# MARS_PORB.net
KiCad netlist of a schematic drawn in Altium Designer
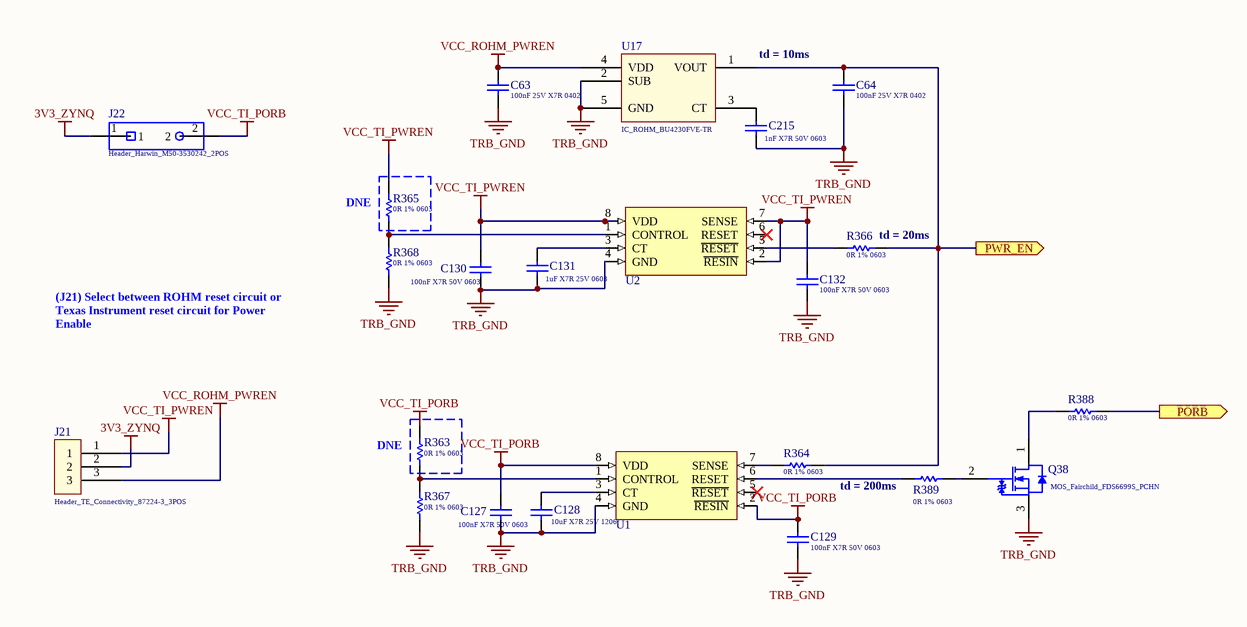
[diagram p0: MARS_PORB.SchDoc]

(export (version "E")
  (design (tool "Eeschema 10.0.6"))
  (components
    (comp (ref "C63")
      (value "Cap_Taiyo_Yuden_TMK105B7104KV-FR_100nF")
      (footprint "Cap_Taiyo_Yuden_TMK105B7104KV-FR_100nF")
      (description "CAP CER 100nF 25V X7R 0402")
      (fields (field (name "CAPACITANCE") "100nF 25V X7R 0402"))
      (libsource (lib "Cap_Taiyo_Yuden_TMK105B7104KV-FR_100nF") (part "Cap_Taiyo_Yuden_TMK105B7104KV-FR_100nF"))
    )
    (comp (ref "C64")
      (value "Cap_Taiyo_Yuden_TMK105B7104KV-FR_100nF")
      (footprint "Cap_Taiyo_Yuden_TMK105B7104KV-FR_100nF")
      (description "CAP CER 100nF 25V X7R 0402")
      (fields (field (name "CAPACITANCE") "100nF 25V X7R 0402"))
      (libsource (lib "Cap_Taiyo_Yuden_TMK105B7104KV-FR_100nF") (part "Cap_Taiyo_Yuden_TMK105B7104KV-FR_100nF"))
    )
    (comp (ref "C127")
      (value "Cap_Kemet_C0603C104M5RACAUTO_100nF")
      (footprint "Cap_Kemet_C0603C104M5RACAUTO_100nF")
      (description "CAP CER 100nF 50V X7R 0603")
      (fields (field (name "CAPACITANCE") "100nF X7R 50V 0603"))
      (libsource (lib "Cap_Kemet_C0603C104M5RACAUTO_100nF") (part "Cap_Kemet_C0603C104M5RACAUTO_100nF"))
    )
    (comp (ref "C128")
      (value "Cap_Murata_GRM31CR71E106MA12L_10uF")
      (footprint "Cap_Murata_GRM31CR71E106MA12L_10uF")
      (description "CAP CER 10uF 25V X7R 1206")
      (fields (field (name "CAPACITANCE") "10uF X7R 25V 1206"))
      (libsource (lib "Cap_Murata_GRM31CR71E106MA12L_10uF") (part "Cap_Murata_GRM31CR71E106MA12L_10uF"))
    )
    (comp (ref "C129")
      (value "Cap_Kemet_C0603C104M5RACAUTO_100nF")
      (footprint "Cap_Kemet_C0603C104M5RACAUTO_100nF")
      (description "CAP CER 100nF 50V X7R 0603")
      (fields (field (name "CAPACITANCE") "100nF X7R 50V 0603"))
      (libsource (lib "Cap_Kemet_C0603C104M5RACAUTO_100nF") (part "Cap_Kemet_C0603C104M5RACAUTO_100nF"))
    )
    (comp (ref "C130")
      (value "Cap_Kemet_C0603C104M5RACAUTO_100nF")
      (footprint "Cap_Kemet_C0603C104M5RACAUTO_100nF")
      (description "CAP CER 100nF 50V X7R 0603")
      (fields (field (name "CAPACITANCE") "100nF X7R 50V 0603"))
      (libsource (lib "Cap_Kemet_C0603C104M5RACAUTO_100nF") (part "Cap_Kemet_C0603C104M5RACAUTO_100nF"))
    )
    (comp (ref "C131")
      (value "Cap_Murata_GCJ188R71E105KA01J_1uF")
      (footprint "Cap_Murata_GCJ188R71E105KA01J_1uF")
      (description "CAP CER 1uF 25V X7R 0603")
      (fields (field (name "CAPACITANCE") "1uF X7R 25V 0603"))
      (libsource (lib "Cap_Murata_GCJ188R71E105KA01J_1uF") (part "Cap_Murata_GCJ188R71E105KA01J_1uF"))
    )
    (comp (ref "C132")
      (value "Cap_Kemet_C0603C104M5RACAUTO_100nF")
      (footprint "Cap_Kemet_C0603C104M5RACAUTO_100nF")
      (description "CAP CER 100nF 50V X7R 0603")
      (fields (field (name "CAPACITANCE") "100nF X7R 50V 0603"))
      (libsource (lib "Cap_Kemet_C0603C104M5RACAUTO_100nF") (part "Cap_Kemet_C0603C104M5RACAUTO_100nF"))
    )
    (comp (ref "C215")
      (value "Cap_Kemet_C0603C102J5RACAUTO_1nF")
      (footprint "Cap_Kemet_C0603C102J5RACAUTO_1nF")
      (description "CAP CER 1nF 50V X7R 0603")
      (fields (field (name "CAPACITANCE") "1nF X7R 50V 0603"))
      (libsource (lib "Cap_Kemet_C0603C102J5RACAUTO_1nF") (part "Cap_Kemet_C0603C102J5RACAUTO_1nF"))
    )
    (comp (ref "J21")
      (value "Header_TE_Connectivity_87224-3_3POS")
      (footprint "Header_TE_Connectivity_87224-3_3POS")
      (description "Headers & Wire Housings UNSHRD VERT SNGL 3")
      (libsource (lib "Header_TE_Connectivity_87224-3_3POS") (part "Header_TE_Connectivity_87224-3_3POS"))
    )
    (comp (ref "J22")
      (value "Header_Harwin_M50-3530242_2POS")
      (footprint "Header_Harwin_M50-3530242_2POS")
      (description "Headers & Wire Housings 2 WAY SIL VERT PC TAIL P/HDR")
      (libsource (lib "Header_Harwin_M50-3530242_2POS") (part "Header_Harwin_M50-3530242_2POS"))
    )
    (comp (ref "Q38")
      (value "MOS_Fairchild_FDS6699S_PCHN")
      (footprint "MOS_Fairchild_FDS6699S_PCHN")
      (description "MOSFET 30V N-Ch PowerTrench SyncFET")
      (libsource (lib "MOS_Fairchild_FDS6699S_PCHN") (part "MOS_Fairchild_FDS6699S_PCHN"))
    )
    (comp (ref "R363")
      (value "Res_Vishay_CRCW06030000Z0EAHP_0_Ohm")
      (footprint "Res_Vishay_CRCW06030000Z0EAHP_0_Ohm_duplicate")
      (description "0R 0.25W 1% 0603 (1608 Metric)  SMD")
      (fields (field (name "RESISTANCE") "0R 1% 0603"))
      (libsource (lib "Res_Vishay_CRCW06030000Z0EAHP_0_Ohm") (part "Res_Vishay_CRCW06030000Z0EAHP_0_Ohm"))
    )
    (comp (ref "R364")
      (value "Res_Vishay_CRCW06030000Z0EAHP_0_Ohm")
      (footprint "Res_Vishay_CRCW06030000Z0EAHP_0_Ohm_duplicate")
      (description "0R 0.25W 1% 0603 (1608 Metric)  SMD")
      (fields (field (name "RESISTANCE") "0R 1% 0603"))
      (libsource (lib "Res_Vishay_CRCW06030000Z0EAHP_0_Ohm") (part "Res_Vishay_CRCW06030000Z0EAHP_0_Ohm"))
    )
    (comp (ref "R365")
      (value "Res_Vishay_CRCW06030000Z0EAHP_0_Ohm")
      (footprint "Res_Vishay_CRCW06030000Z0EAHP_0_Ohm_duplicate")
      (description "0R 0.25W 1% 0603 (1608 Metric)  SMD")
      (fields (field (name "RESISTANCE") "0R 1% 0603"))
      (libsource (lib "Res_Vishay_CRCW06030000Z0EAHP_0_Ohm") (part "Res_Vishay_CRCW06030000Z0EAHP_0_Ohm"))
    )
    (comp (ref "R366")
      (value "Res_Vishay_CRCW06030000Z0EAHP_0_Ohm")
      (footprint "Res_Vishay_CRCW06030000Z0EAHP_0_Ohm_duplicate")
      (description "0R 0.25W 1% 0603 (1608 Metric)  SMD")
      (fields (field (name "RESISTANCE") "0R 1% 0603"))
      (libsource (lib "Res_Vishay_CRCW06030000Z0EAHP_0_Ohm") (part "Res_Vishay_CRCW06030000Z0EAHP_0_Ohm"))
    )
    (comp (ref "R367")
      (value "Res_Vishay_CRCW06030000Z0EAHP_0_Ohm")
      (footprint "Res_Vishay_CRCW06030000Z0EAHP_0_Ohm_duplicate")
      (description "0R 0.25W 1% 0603 (1608 Metric)  SMD")
      (fields (field (name "RESISTANCE") "0R 1% 0603"))
      (libsource (lib "Res_Vishay_CRCW06030000Z0EAHP_0_Ohm") (part "Res_Vishay_CRCW06030000Z0EAHP_0_Ohm"))
    )
    (comp (ref "R368")
      (value "Res_Vishay_CRCW06030000Z0EAHP_0_Ohm")
      (footprint "Res_Vishay_CRCW06030000Z0EAHP_0_Ohm_duplicate")
      (description "0R 0.25W 1% 0603 (1608 Metric)  SMD")
      (fields (field (name "RESISTANCE") "0R 1% 0603"))
      (libsource (lib "Res_Vishay_CRCW06030000Z0EAHP_0_Ohm") (part "Res_Vishay_CRCW06030000Z0EAHP_0_Ohm"))
    )
    (comp (ref "R388")
      (value "Res_Vishay_CRCW06030000Z0EAHP_0_Ohm")
      (footprint "Res_Vishay_CRCW06030000Z0EAHP_0_Ohm_duplicate")
      (description "0R 0.25W 1% 0603 (1608 Metric)  SMD")
      (fields (field (name "RESISTANCE") "0R 1% 0603"))
      (libsource (lib "Res_Vishay_CRCW06030000Z0EAHP_0_Ohm") (part "Res_Vishay_CRCW06030000Z0EAHP_0_Ohm"))
    )
    (comp (ref "R389")
      (value "Res_Vishay_CRCW06030000Z0EAHP_0_Ohm")
      (footprint "Res_Vishay_CRCW06030000Z0EAHP_0_Ohm_duplicate")
      (description "0R 0.25W 1% 0603 (1608 Metric)  SMD")
      (fields (field (name "RESISTANCE") "0R 1% 0603"))
      (libsource (lib "Res_Vishay_CRCW06030000Z0EAHP_0_Ohm") (part "Res_Vishay_CRCW06030000Z0EAHP_0_Ohm"))
    )
    (comp (ref "U1")
      (value "PMU_Texas_Instruments_TLC7733IPWR_2.93")
      (footprint "PMU_Texas_Instruments_TLC7733IPWR_2.93")
      (description "Supervisory Circuits 2.93V Monitor")
      (libsource (lib "PMU_Texas_Instruments_TLC7733IPWR_2.93") (part "PMU_Texas_Instruments_TLC7733IPWR_2.93"))
    )
    (comp (ref "U2")
      (value "PMU_Texas_Instruments_TLC7733IPWR_2.93")
      (footprint "PMU_Texas_Instruments_TLC7733IPWR_2.93")
      (description "Supervisory Circuits 2.93V Monitor")
      (libsource (lib "PMU_Texas_Instruments_TLC7733IPWR_2.93") (part "PMU_Texas_Instruments_TLC7733IPWR_2.93"))
    )
    (comp (ref "U17")
      (value "IC_ROHM_BU4230FVE-TR")
      (footprint "IC_ROHM_BU4230FVE-TR")
      (description "Supervisory Circuits LOW VOLT DETECT VOL")
      (libsource (lib "IC_ROHM_BU4230FVE-TR") (part "IC_ROHM_BU4230FVE-TR"))
    )
  )
  (nets
    (net (code "1") (name "/PORB") (class "Default")
      (node (ref "R388") (pin "1") (pinfunction "1_1") (pintype "passive"))
    )
    (net (code "2") (name "/PWR_EN") (class "Default")
      (node (ref "C64") (pin "1") (pinfunction "1_1") (pintype "passive"))
      (node (ref "R364") (pin "1") (pinfunction "1_1") (pintype "passive"))
      (node (ref "R366") (pin "1") (pinfunction "1_1") (pintype "passive"))
      (node (ref "U17") (pin "1") (pinfunction "VOUT_1") (pintype "passive"))
    )
    (net (code "3") (name "3V3_ZYNQ") (class "Default")
      (node (ref "J21") (pin "2") (pinfunction "2_2") (pintype "passive"))
      (node (ref "J22") (pin "1") (pinfunction "1_1") (pintype "passive"))
    )
    (net (code "4") (name "Net-(Q38-D)") (class "Default")
      (node (ref "Q38") (pin "1") (pinfunction "D_1") (pintype "passive"))
      (node (ref "R388") (pin "2") (pinfunction "2_2") (pintype "passive"))
    )
    (net (code "5") (name "Net-(Q38-G)") (class "Default")
      (node (ref "Q38") (pin "2") (pinfunction "G_2") (pintype "passive"))
      (node (ref "R389") (pin "1") (pinfunction "1_1") (pintype "passive"))
    )
    (net (code "6") (name "Net-(U1-CONTROL)") (class "Default")
      (node (ref "R363") (pin "1") (pinfunction "1_1") (pintype "passive"))
      (node (ref "R367") (pin "2") (pinfunction "2_2") (pintype "passive"))
      (node (ref "U1") (pin "1") (pinfunction "CONTROL_1") (pintype "input"))
    )
    (net (code "7") (name "Net-(U1-CT)") (class "Default")
      (node (ref "C128") (pin "1") (pinfunction "1_1") (pintype "passive"))
      (node (ref "U1") (pin "3") (pinfunction "CT_3") (pintype "input"))
    )
    (net (code "8") (name "Net-(U1-RESET)") (class "Default")
      (node (ref "R389") (pin "2") (pinfunction "2_2") (pintype "passive"))
      (node (ref "U1") (pin "6") (pinfunction "RESET_6") (pintype "input"))
    )
    (net (code "9") (name "Net-(U1-SENSE)") (class "Default")
      (node (ref "R364") (pin "2") (pinfunction "2_2") (pintype "passive"))
      (node (ref "U1") (pin "7") (pinfunction "SENSE_7") (pintype "input"))
    )
    (net (code "10") (name "Net-(U2-CONTROL)") (class "Default")
      (node (ref "R365") (pin "2") (pinfunction "2_2") (pintype "passive"))
      (node (ref "R368") (pin "2") (pinfunction "2_2") (pintype "passive"))
      (node (ref "U2") (pin "1") (pinfunction "CONTROL_1") (pintype "input"))
    )
    (net (code "11") (name "Net-(U2-CT)") (class "Default")
      (node (ref "C131") (pin "2") (pinfunction "2_2") (pintype "passive"))
      (node (ref "U2") (pin "3") (pinfunction "CT_3") (pintype "input"))
    )
    (net (code "12") (name "Net-(U2-~{RESET})") (class "Default")
      (node (ref "R366") (pin "2") (pinfunction "2_2") (pintype "passive"))
      (node (ref "U2") (pin "5") (pinfunction "~{RESET}_5") (pintype "input"))
    )
    (net (code "13") (name "Net-(U17-CT)") (class "Default")
      (node (ref "C215") (pin "2") (pinfunction "2_2") (pintype "passive"))
      (node (ref "U17") (pin "3") (pinfunction "CT_3") (pintype "passive"))
    )
    (net (code "14") (name "TRB_GND") (class "Default")
      (node (ref "C127") (pin "2") (pinfunction "2_2") (pintype "passive"))
      (node (ref "C128") (pin "2") (pinfunction "2_2") (pintype "passive"))
      (node (ref "C129") (pin "2") (pinfunction "2_2") (pintype "passive"))
      (node (ref "C130") (pin "2") (pinfunction "2_2") (pintype "passive"))
      (node (ref "C131") (pin "1") (pinfunction "1_1") (pintype "passive"))
      (node (ref "C132") (pin "2") (pinfunction "2_2") (pintype "passive"))
      (node (ref "C215") (pin "1") (pinfunction "1_1") (pintype "passive"))
      (node (ref "C63") (pin "1") (pinfunction "1_1") (pintype "passive"))
      (node (ref "C64") (pin "2") (pinfunction "2_2") (pintype "passive"))
      (node (ref "Q38") (pin "3") (pinfunction "S_3") (pintype "passive"))
      (node (ref "R367") (pin "1") (pinfunction "1_1") (pintype "passive"))
      (node (ref "R368") (pin "1") (pinfunction "1_1") (pintype "passive"))
      (node (ref "U1") (pin "4") (pinfunction "GND_4") (pintype "input"))
      (node (ref "U17") (pin "2") (pinfunction "SUB_2") (pintype "passive"))
      (node (ref "U17") (pin "5") (pinfunction "GND_5") (pintype "passive"))
      (node (ref "U2") (pin "4") (pinfunction "GND_4") (pintype "input"))
    )
    (net (code "15") (name "VCC_ROHM_PWREN") (class "Default")
      (node (ref "C63") (pin "2") (pinfunction "2_2") (pintype "passive"))
      (node (ref "J21") (pin "3") (pinfunction "3_3") (pintype "passive"))
      (node (ref "U17") (pin "4") (pinfunction "VDD_4") (pintype "passive"))
    )
    (net (code "16") (name "VCC_TI_PORB") (class "Default")
      (node (ref "C127") (pin "1") (pinfunction "1_1") (pintype "passive"))
      (node (ref "C129") (pin "1") (pinfunction "1_1") (pintype "passive"))
      (node (ref "J22") (pin "2") (pinfunction "2_2") (pintype "passive"))
      (node (ref "R363") (pin "2") (pinfunction "2_2") (pintype "passive"))
      (node (ref "U1") (pin "2") (pinfunction "~{RESIN}_2") (pintype "input"))
      (node (ref "U1") (pin "8") (pinfunction "VDD_8") (pintype "input"))
    )
    (net (code "17") (name "VCC_TI_PWREN") (class "Default")
      (node (ref "C130") (pin "1") (pinfunction "1_1") (pintype "passive"))
      (node (ref "C132") (pin "1") (pinfunction "1_1") (pintype "passive"))
      (node (ref "J21") (pin "1") (pinfunction "1_1") (pintype "passive"))
      (node (ref "R365") (pin "1") (pinfunction "1_1") (pintype "passive"))
      (node (ref "U2") (pin "2") (pinfunction "~{RESIN}_2") (pintype "input"))
      (node (ref "U2") (pin "7") (pinfunction "SENSE_7") (pintype "input"))
      (node (ref "U2") (pin "8") (pinfunction "VDD_8") (pintype "input"))
    )
    (net (code "18") (name "unconnected-(U1-~{RESET}-Pad5)") (class "Default")
      (node (ref "U1") (pin "5") (pinfunction "~{RESET}_5") (pintype "input+no_connect"))
    )
    (net (code "19") (name "unconnected-(U2-RESET-Pad6)") (class "Default")
      (node (ref "U2") (pin "6") (pinfunction "RESET_6") (pintype "input+no_connect"))
    )
  )
)
